# DRV8701ESheet.net
KiCad netlist of a schematic drawn in Altium Designer
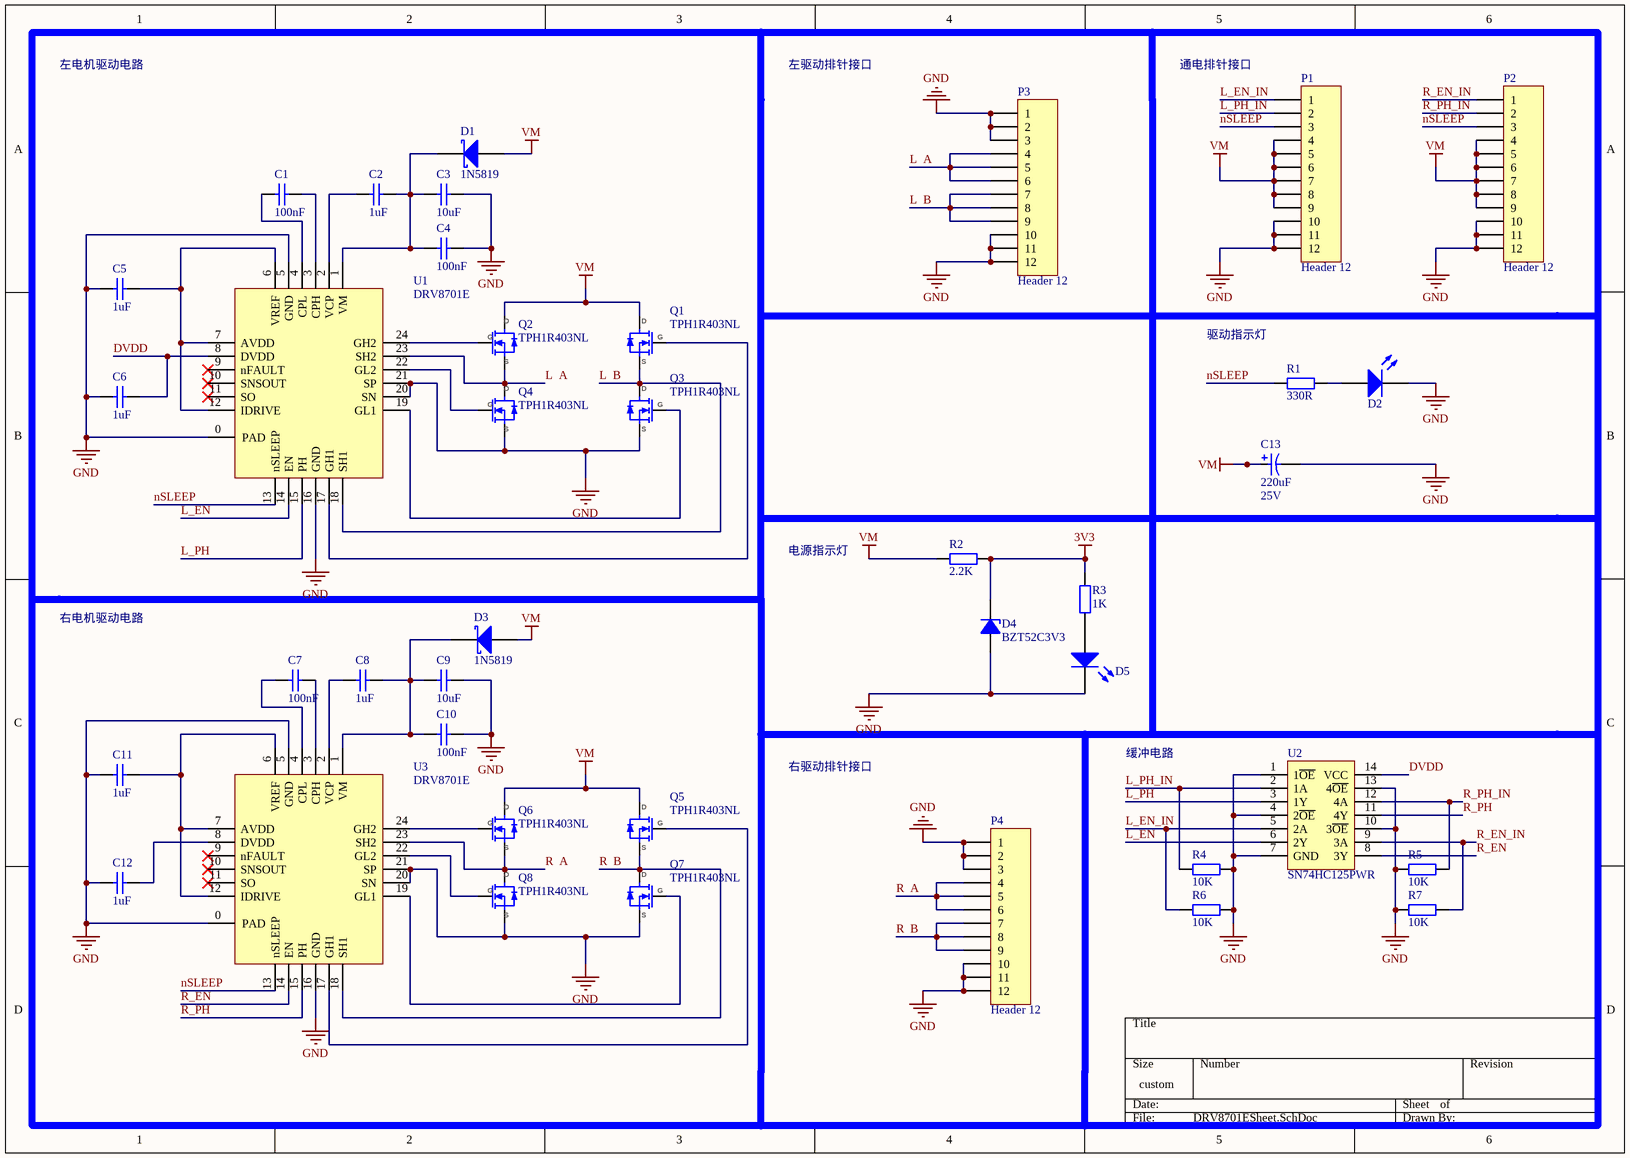
[diagram p0: DRV8701ESheet.SchDoc]

(export (version "E")
  (design (tool "Eeschema 10.0.6"))
  (components
    (comp (ref "C1")
      (value "100nF")
      (footprint "C0603_L")
      (description "贴片电容")
      (libsource (lib "0.1_电容&电感&电阻&保险丝") (part "C-SMD"))
    )
    (comp (ref "C2")
      (value "1uF")
      (footprint "C0603_L")
      (description "贴片电容")
      (libsource (lib "0.1_电容&电感&电阻&保险丝") (part "C-SMD"))
    )
    (comp (ref "C3")
      (value "10uF")
      (footprint "C0603_L")
      (description "贴片电容")
      (libsource (lib "0.1_电容&电感&电阻&保险丝") (part "C-SMD"))
    )
    (comp (ref "C4")
      (value "100nF")
      (footprint "C0603_L")
      (description "贴片电容")
      (libsource (lib "0.1_电容&电感&电阻&保险丝") (part "C-SMD"))
    )
    (comp (ref "C5")
      (value "1uF")
      (footprint "C0603_L")
      (description "贴片电容")
      (libsource (lib "0.1_电容&电感&电阻&保险丝") (part "C-SMD"))
    )
    (comp (ref "C6")
      (value "1uF")
      (footprint "C0603_L")
      (description "贴片电容")
      (libsource (lib "0.1_电容&电感&电阻&保险丝") (part "C-SMD"))
    )
    (comp (ref "C7")
      (value "100nF")
      (footprint "C0603_L")
      (description "贴片电容")
      (libsource (lib "0.1_电容&电感&电阻&保险丝") (part "C-SMD"))
    )
    (comp (ref "C8")
      (value "1uF")
      (footprint "C0603_L")
      (description "贴片电容")
      (libsource (lib "0.1_电容&电感&电阻&保险丝") (part "C-SMD"))
    )
    (comp (ref "C9")
      (value "10uF")
      (footprint "C0603_L")
      (description "贴片电容")
      (libsource (lib "0.1_电容&电感&电阻&保险丝") (part "C-SMD"))
    )
    (comp (ref "C10")
      (value "100nF")
      (footprint "C0603_L")
      (description "贴片电容")
      (libsource (lib "0.1_电容&电感&电阻&保险丝") (part "C-SMD"))
    )
    (comp (ref "C11")
      (value "1uF")
      (footprint "C0603_L")
      (description "贴片电容")
      (libsource (lib "0.1_电容&电感&电阻&保险丝") (part "C-SMD"))
    )
    (comp (ref "C12")
      (value "1uF")
      (footprint "C0603_L")
      (description "贴片电容")
      (libsource (lib "0.1_电容&电感&电阻&保险丝") (part "C-SMD"))
    )
    (comp (ref "C13")
      (value "220uF")
      (footprint "CAPPR3.5-8X11.5")
      (description "Polarized Capacitor (Radial)")
      (fields
        (field (name "VOLTAGE") "25V")
        (field (name "Comment") "220uF 25V")
        (field (name "PUBLISHER") "Altium Limited")
      )
      (libsource (lib "DRV8701E 双驱V1.1 集成封装库") (part "Cap-Elect"))
    )
    (comp (ref "D1")
      (value "1N5819")
      (footprint "SOD-323")
      (description "肖特基二极管")
      (libsource (lib "0.2_二极管&整流桥") (part "1N5819"))
    )
    (comp (ref "D2")
      (value "LED")
      (footprint "LED-0603_R")
      (description "贴片发光二极管")
      (libsource (lib "0.3_LED发光二极管") (part "LED_SMD"))
    )
    (comp (ref "D3")
      (value "1N5819")
      (footprint "SOD-323")
      (description "肖特基二极管")
      (libsource (lib "0.2_二极管&整流桥") (part "1N5819"))
    )
    (comp (ref "D4")
      (value "BZT52C3V3")
      (footprint "SOD-123-L")
      (description "3.3V稳压二极管")
      (fields (field (name "PUBLISHER") "Altium Limited"))
      (libsource (lib "智能车驱动板DRV8701E") (part "Diode Zen"))
    )
    (comp (ref "D5")
      (value "LED")
      (footprint "LED-0603_R")
      (description "贴片发光二极管")
      (libsource (lib "智能车驱动板DRV8701E") (part "LED_SMD"))
    )
    (comp (ref "P1")
      (value "Header 12")
      (footprint "HDR1X12")
      (description "Header, 12-Pin")
      (fields (field (name "PUBLISHER") "Altium Limited"))
      (libsource (lib "Miscellaneous Connectors") (part "Header 12"))
    )
    (comp (ref "P2")
      (value "Header 12")
      (footprint "HDR1X12")
      (description "Header, 12-Pin")
      (fields (field (name "PUBLISHER") "Altium Limited"))
      (libsource (lib "Miscellaneous Connectors") (part "Header 12"))
    )
    (comp (ref "P3")
      (value "Header 12")
      (footprint "HDR1X12")
      (description "Header, 12-Pin")
      (fields (field (name "PUBLISHER") "Altium Limited"))
      (libsource (lib "Miscellaneous Connectors") (part "Header 12"))
    )
    (comp (ref "P4")
      (value "Header 12")
      (footprint "HDR1X12")
      (description "Header, 12-Pin")
      (fields (field (name "PUBLISHER") "Altium Limited"))
      (libsource (lib "Miscellaneous Connectors") (part "Header 12"))
    )
    (comp (ref "Q1")
      (value "TPH1R403NL")
      (footprint "DFN5x6")
      (description "N沟道MOS")
      (libsource (lib "0.4_场效应管&可控硅") (part "TPH1R403NL"))
    )
    (comp (ref "Q2")
      (value "TPH1R403NL")
      (footprint "DFN5x6")
      (description "N沟道MOS")
      (libsource (lib "0.4_场效应管&可控硅") (part "TPH1R403NL"))
    )
    (comp (ref "Q3")
      (value "TPH1R403NL")
      (footprint "DFN5x6")
      (description "N沟道MOS")
      (libsource (lib "0.4_场效应管&可控硅") (part "TPH1R403NL"))
    )
    (comp (ref "Q4")
      (value "TPH1R403NL")
      (footprint "DFN5x6")
      (description "N沟道MOS")
      (libsource (lib "0.4_场效应管&可控硅") (part "TPH1R403NL"))
    )
    (comp (ref "Q5")
      (value "TPH1R403NL")
      (footprint "DFN5x6")
      (description "N沟道MOS")
      (libsource (lib "0.4_场效应管&可控硅") (part "TPH1R403NL"))
    )
    (comp (ref "Q6")
      (value "TPH1R403NL")
      (footprint "DFN5x6")
      (description "N沟道MOS")
      (libsource (lib "0.4_场效应管&可控硅") (part "TPH1R403NL"))
    )
    (comp (ref "Q7")
      (value "TPH1R403NL")
      (footprint "DFN5x6")
      (description "N沟道MOS")
      (libsource (lib "0.4_场效应管&可控硅") (part "TPH1R403NL"))
    )
    (comp (ref "Q8")
      (value "TPH1R403NL")
      (footprint "DFN5x6")
      (description "N沟道MOS")
      (libsource (lib "0.4_场效应管&可控硅") (part "TPH1R403NL"))
    )
    (comp (ref "R1")
      (value "330R")
      (footprint "R0603_L")
      (description "贴片电阻")
      (libsource (lib "0.1_电容&电感&电阻&保险丝") (part "R-SMD"))
    )
    (comp (ref "R2")
      (value "2.2K")
      (footprint "R0603_L")
      (description "贴片电阻")
      (libsource (lib "0.1_电容&电感&电阻&保险丝") (part "R-SMD"))
    )
    (comp (ref "R3")
      (value "1K")
      (footprint "R0603_L")
      (description "贴片电阻")
      (libsource (lib "智能车驱动板DRV8701E") (part "R-SMD"))
    )
    (comp (ref "R4")
      (value "10K")
      (footprint "R0603_L")
      (description "贴片电阻")
      (libsource (lib "0.1_电容&电感&电阻&保险丝") (part "R-SMD"))
    )
    (comp (ref "R5")
      (value "10K")
      (footprint "R0603_L")
      (description "贴片电阻")
      (libsource (lib "0.1_电容&电感&电阻&保险丝") (part "R-SMD"))
    )
    (comp (ref "R6")
      (value "10K")
      (footprint "R0603_L")
      (description "贴片电阻")
      (libsource (lib "0.1_电容&电感&电阻&保险丝") (part "R-SMD"))
    )
    (comp (ref "R7")
      (value "10K")
      (footprint "R0603_L")
      (description "贴片电阻")
      (libsource (lib "0.1_电容&电感&电阻&保险丝") (part "R-SMD"))
    )
    (comp (ref "U1")
      (value "DRV8701E")
      (footprint "QFN24-4x4")
      (description "DRV8701E Ti全桥驱动芯片")
      (libsource (lib "智能车驱动板DRV8701E") (part "DRV8701E"))
    )
    (comp (ref "U2")
      (value "SN74HC125PWR")
      (footprint "TSSOP14")
      (description "三态输出的四路缓冲器")
      (libsource (lib "智能车驱动板DRV8701E") (part "SN74HC125PWR"))
    )
    (comp (ref "U3")
      (value "DRV8701E")
      (footprint "QFN24-4x4")
      (description "DRV8701E Ti全桥驱动芯片")
      (libsource (lib "智能车驱动板DRV8701E") (part "DRV8701E"))
    )
  )
  (nets
    (net (code "1") (name "/DVDD") (class "Default")
      (node (ref "C6") (pin "2") (pinfunction "2_2") (pintype "passive"))
      (node (ref "U1") (pin "8") (pinfunction "DVDD_8") (pintype "passive"))
      (node (ref "U2") (pin "14") (pinfunction "VCC_14") (pintype "passive"))
    )
    (net (code "2") (name "/L  A") (class "Default")
      (node (ref "P3") (pin "4") (pinfunction "4_4") (pintype "passive"))
      (node (ref "P3") (pin "5") (pinfunction "5_5") (pintype "passive"))
      (node (ref "P3") (pin "6") (pinfunction "6_6") (pintype "passive"))
      (node (ref "Q2") (pin "3") (pinfunction "S_3") (pintype "passive"))
      (node (ref "Q4") (pin "1") (pinfunction "D_1") (pintype "passive"))
      (node (ref "U1") (pin "23") (pinfunction "SH2_23") (pintype "passive"))
    )
    (net (code "3") (name "/L  B") (class "Default")
      (node (ref "P3") (pin "7") (pinfunction "7_7") (pintype "passive"))
      (node (ref "P3") (pin "8") (pinfunction "8_8") (pintype "passive"))
      (node (ref "P3") (pin "9") (pinfunction "9_9") (pintype "passive"))
      (node (ref "Q1") (pin "3") (pinfunction "S_3") (pintype "passive"))
      (node (ref "Q3") (pin "1") (pinfunction "D_1") (pintype "passive"))
      (node (ref "U1") (pin "18") (pinfunction "SH1_18") (pintype "passive"))
    )
    (net (code "4") (name "/L_EN") (class "Default")
      (node (ref "U1") (pin "14") (pinfunction "EN_14") (pintype "passive"))
      (node (ref "U2") (pin "6") (pinfunction "2Y_6") (pintype "passive"))
    )
    (net (code "5") (name "/L_EN_IN") (class "Default")
      (node (ref "P1") (pin "1") (pinfunction "1_1") (pintype "passive"))
      (node (ref "R6") (pin "1") (pinfunction "1_1") (pintype "passive"))
      (node (ref "U2") (pin "5") (pinfunction "2A_5") (pintype "passive"))
    )
    (net (code "6") (name "/L_PH") (class "Default")
      (node (ref "U1") (pin "15") (pinfunction "PH_15") (pintype "passive"))
      (node (ref "U2") (pin "3") (pinfunction "1Y_3") (pintype "passive"))
    )
    (net (code "7") (name "/L_PH_IN") (class "Default")
      (node (ref "P1") (pin "2") (pinfunction "2_2") (pintype "passive"))
      (node (ref "R4") (pin "1") (pinfunction "1_1") (pintype "passive"))
      (node (ref "U2") (pin "2") (pinfunction "1A_2") (pintype "passive"))
    )
    (net (code "8") (name "/R  A") (class "Default")
      (node (ref "P4") (pin "4") (pinfunction "4_4") (pintype "passive"))
      (node (ref "P4") (pin "5") (pinfunction "5_5") (pintype "passive"))
      (node (ref "P4") (pin "6") (pinfunction "6_6") (pintype "passive"))
      (node (ref "Q6") (pin "3") (pinfunction "S_3") (pintype "passive"))
      (node (ref "Q8") (pin "1") (pinfunction "D_1") (pintype "passive"))
      (node (ref "U3") (pin "23") (pinfunction "SH2_23") (pintype "passive"))
    )
    (net (code "9") (name "/R  B") (class "Default")
      (node (ref "P4") (pin "7") (pinfunction "7_7") (pintype "passive"))
      (node (ref "P4") (pin "8") (pinfunction "8_8") (pintype "passive"))
      (node (ref "P4") (pin "9") (pinfunction "9_9") (pintype "passive"))
      (node (ref "Q5") (pin "3") (pinfunction "S_3") (pintype "passive"))
      (node (ref "Q7") (pin "1") (pinfunction "D_1") (pintype "passive"))
      (node (ref "U3") (pin "18") (pinfunction "SH1_18") (pintype "passive"))
    )
    (net (code "10") (name "/R_EN") (class "Default")
      (node (ref "U2") (pin "8") (pinfunction "3Y_8") (pintype "passive"))
      (node (ref "U3") (pin "14") (pinfunction "EN_14") (pintype "passive"))
    )
    (net (code "11") (name "/R_EN_IN") (class "Default")
      (node (ref "P2") (pin "1") (pinfunction "1_1") (pintype "passive"))
      (node (ref "R7") (pin "2") (pinfunction "2_2") (pintype "passive"))
      (node (ref "U2") (pin "9") (pinfunction "3A_9") (pintype "passive"))
    )
    (net (code "12") (name "/R_PH") (class "Default")
      (node (ref "U2") (pin "11") (pinfunction "4Y_11") (pintype "passive"))
      (node (ref "U3") (pin "15") (pinfunction "PH_15") (pintype "passive"))
    )
    (net (code "13") (name "/R_PH_IN") (class "Default")
      (node (ref "P2") (pin "2") (pinfunction "2_2") (pintype "passive"))
      (node (ref "R5") (pin "2") (pinfunction "2_2") (pintype "passive"))
      (node (ref "U2") (pin "12") (pinfunction "4A_12") (pintype "passive"))
    )
    (net (code "14") (name "/nSLEEP") (class "Default")
      (node (ref "P1") (pin "3") (pinfunction "3_3") (pintype "passive"))
      (node (ref "P2") (pin "3") (pinfunction "3_3") (pintype "passive"))
      (node (ref "R1") (pin "1") (pinfunction "1_1") (pintype "passive"))
      (node (ref "U1") (pin "13") (pinfunction "nSLEEP_13") (pintype "passive"))
      (node (ref "U3") (pin "13") (pinfunction "nSLEEP_13") (pintype "passive"))
    )
    (net (code "15") (name "3V3") (class "Default")
      (node (ref "D4") (pin "K") (pinfunction "K_K") (pintype "passive"))
      (node (ref "R2") (pin "2") (pinfunction "2_2") (pintype "passive"))
      (node (ref "R3") (pin "2") (pinfunction "2_2") (pintype "passive"))
    )
    (net (code "16") (name "GND") (class "Default")
      (node (ref "C10") (pin "2") (pinfunction "2_2") (pintype "passive"))
      (node (ref "C11") (pin "1") (pinfunction "1_1") (pintype "passive"))
      (node (ref "C12") (pin "1") (pinfunction "1_1") (pintype "passive"))
      (node (ref "C13") (pin "2") (pinfunction "2_2") (pintype "passive"))
      (node (ref "C3") (pin "2") (pinfunction "2_2") (pintype "passive"))
      (node (ref "C4") (pin "2") (pinfunction "2_2") (pintype "passive"))
      (node (ref "C5") (pin "1") (pinfunction "1_1") (pintype "passive"))
      (node (ref "C6") (pin "1") (pinfunction "1_1") (pintype "passive"))
      (node (ref "C9") (pin "2") (pinfunction "2_2") (pintype "passive"))
      (node (ref "D2") (pin "2") (pinfunction "K_2") (pintype "passive"))
      (node (ref "D4") (pin "A") (pinfunction "A_A") (pintype "passive"))
      (node (ref "D5") (pin "2") (pinfunction "K_2") (pintype "passive"))
      (node (ref "P1") (pin "10") (pinfunction "10_10") (pintype "passive"))
      (node (ref "P1") (pin "11") (pinfunction "11_11") (pintype "passive"))
      (node (ref "P1") (pin "12") (pinfunction "12_12") (pintype "passive"))
      (node (ref "P2") (pin "10") (pinfunction "10_10") (pintype "passive"))
      (node (ref "P2") (pin "11") (pinfunction "11_11") (pintype "passive"))
      (node (ref "P2") (pin "12") (pinfunction "12_12") (pintype "passive"))
      (node (ref "P3") (pin "1") (pinfunction "1_1") (pintype "passive"))
      (node (ref "P3") (pin "10") (pinfunction "10_10") (pintype "passive"))
      (node (ref "P3") (pin "11") (pinfunction "11_11") (pintype "passive"))
      (node (ref "P3") (pin "12") (pinfunction "12_12") (pintype "passive"))
      (node (ref "P3") (pin "2") (pinfunction "2_2") (pintype "passive"))
      (node (ref "P3") (pin "3") (pinfunction "3_3") (pintype "passive"))
      (node (ref "P4") (pin "1") (pinfunction "1_1") (pintype "passive"))
      (node (ref "P4") (pin "10") (pinfunction "10_10") (pintype "passive"))
      (node (ref "P4") (pin "11") (pinfunction "11_11") (pintype "passive"))
      (node (ref "P4") (pin "12") (pinfunction "12_12") (pintype "passive"))
      (node (ref "P4") (pin "2") (pinfunction "2_2") (pintype "passive"))
      (node (ref "P4") (pin "3") (pinfunction "3_3") (pintype "passive"))
      (node (ref "Q3") (pin "3") (pinfunction "S_3") (pintype "passive"))
      (node (ref "Q4") (pin "3") (pinfunction "S_3") (pintype "passive"))
      (node (ref "Q7") (pin "3") (pinfunction "S_3") (pintype "passive"))
      (node (ref "Q8") (pin "3") (pinfunction "S_3") (pintype "passive"))
      (node (ref "R4") (pin "2") (pinfunction "2_2") (pintype "passive"))
      (node (ref "R5") (pin "1") (pinfunction "1_1") (pintype "passive"))
      (node (ref "R6") (pin "2") (pinfunction "2_2") (pintype "passive"))
      (node (ref "R7") (pin "1") (pinfunction "1_1") (pintype "passive"))
      (node (ref "U1") (pin "0") (pinfunction "PAD_0") (pintype "passive"))
      (node (ref "U1") (pin "16") (pinfunction "GND_16") (pintype "passive"))
      (node (ref "U1") (pin "20") (pinfunction "SN_20") (pintype "passive"))
      (node (ref "U1") (pin "21") (pinfunction "SP_21") (pintype "passive"))
      (node (ref "U1") (pin "5") (pinfunction "GND_5") (pintype "passive"))
      (node (ref "U2") (pin "1") (pinfunction "1~{OE}_1") (pintype "passive"))
      (node (ref "U2") (pin "10") (pinfunction "3~{OE}_10") (pintype "passive"))
      (node (ref "U2") (pin "13") (pinfunction "4~{OE}_13") (pintype "passive"))
      (node (ref "U2") (pin "4") (pinfunction "2~{OE}_4") (pintype "passive"))
      (node (ref "U2") (pin "7") (pinfunction "GND_7") (pintype "passive"))
      (node (ref "U3") (pin "0") (pinfunction "PAD_0") (pintype "passive"))
      (node (ref "U3") (pin "16") (pinfunction "GND_16") (pintype "passive"))
      (node (ref "U3") (pin "20") (pinfunction "SN_20") (pintype "passive"))
      (node (ref "U3") (pin "21") (pinfunction "SP_21") (pintype "passive"))
      (node (ref "U3") (pin "5") (pinfunction "GND_5") (pintype "passive"))
    )
    (net (code "17") (name "Net-(D1-K)") (class "Default")
      (node (ref "C2") (pin "2") (pinfunction "2_2") (pintype "passive"))
      (node (ref "C3") (pin "1") (pinfunction "1_1") (pintype "passive"))
      (node (ref "C4") (pin "1") (pinfunction "1_1") (pintype "passive"))
      (node (ref "D1") (pin "2") (pinfunction "K_2") (pintype "passive"))
      (node (ref "U1") (pin "1") (pinfunction "VM_1") (pintype "passive"))
    )
    (net (code "18") (name "Net-(D2-A)") (class "Default")
      (node (ref "D2") (pin "1") (pinfunction "A_1") (pintype "passive"))
      (node (ref "R1") (pin "2") (pinfunction "2_2") (pintype "passive"))
    )
    (net (code "19") (name "Net-(D3-K)") (class "Default")
      (node (ref "C10") (pin "1") (pinfunction "1_1") (pintype "passive"))
      (node (ref "C8") (pin "2") (pinfunction "2_2") (pintype "passive"))
      (node (ref "C9") (pin "1") (pinfunction "1_1") (pintype "passive"))
      (node (ref "D3") (pin "2") (pinfunction "K_2") (pintype "passive"))
      (node (ref "U3") (pin "1") (pinfunction "VM_1") (pintype "passive"))
    )
    (net (code "20") (name "Net-(D5-A)") (class "Default")
      (node (ref "D5") (pin "1") (pinfunction "A_1") (pintype "passive"))
      (node (ref "R3") (pin "1") (pinfunction "1_1") (pintype "passive"))
    )
    (net (code "21") (name "Net-(Q1-G)") (class "Default")
      (node (ref "Q1") (pin "2") (pinfunction "G_2") (pintype "passive"))
      (node (ref "U1") (pin "17") (pinfunction "GH1_17") (pintype "passive"))
    )
    (net (code "22") (name "Net-(Q2-G)") (class "Default")
      (node (ref "Q2") (pin "2") (pinfunction "G_2") (pintype "passive"))
      (node (ref "U1") (pin "24") (pinfunction "GH2_24") (pintype "passive"))
    )
    (net (code "23") (name "Net-(Q3-G)") (class "Default")
      (node (ref "Q3") (pin "2") (pinfunction "G_2") (pintype "passive"))
      (node (ref "U1") (pin "19") (pinfunction "GL1_19") (pintype "passive"))
    )
    (net (code "24") (name "Net-(Q4-G)") (class "Default")
      (node (ref "Q4") (pin "2") (pinfunction "G_2") (pintype "passive"))
      (node (ref "U1") (pin "22") (pinfunction "GL2_22") (pintype "passive"))
    )
    (net (code "25") (name "Net-(Q5-G)") (class "Default")
      (node (ref "Q5") (pin "2") (pinfunction "G_2") (pintype "passive"))
      (node (ref "U3") (pin "17") (pinfunction "GH1_17") (pintype "passive"))
    )
    (net (code "26") (name "Net-(Q6-G)") (class "Default")
      (node (ref "Q6") (pin "2") (pinfunction "G_2") (pintype "passive"))
      (node (ref "U3") (pin "24") (pinfunction "GH2_24") (pintype "passive"))
    )
    (net (code "27") (name "Net-(Q7-G)") (class "Default")
      (node (ref "Q7") (pin "2") (pinfunction "G_2") (pintype "passive"))
      (node (ref "U3") (pin "19") (pinfunction "GL1_19") (pintype "passive"))
    )
    (net (code "28") (name "Net-(Q8-G)") (class "Default")
      (node (ref "Q8") (pin "2") (pinfunction "G_2") (pintype "passive"))
      (node (ref "U3") (pin "22") (pinfunction "GL2_22") (pintype "passive"))
    )
    (net (code "29") (name "Net-(U1-AVDD)") (class "Default")
      (node (ref "C5") (pin "2") (pinfunction "2_2") (pintype "passive"))
      (node (ref "U1") (pin "12") (pinfunction "IDRIVE_12") (pintype "passive"))
      (node (ref "U1") (pin "6") (pinfunction "VREF_6") (pintype "passive"))
      (node (ref "U1") (pin "7") (pinfunction "AVDD_7") (pintype "passive"))
    )
    (net (code "30") (name "Net-(U1-CPH)") (class "Default")
      (node (ref "C1") (pin "2") (pinfunction "2_2") (pintype "passive"))
      (node (ref "U1") (pin "3") (pinfunction "CPH_3") (pintype "passive"))
    )
    (net (code "31") (name "Net-(U1-CPL)") (class "Default")
      (node (ref "C1") (pin "1") (pinfunction "1_1") (pintype "passive"))
      (node (ref "U1") (pin "4") (pinfunction "CPL_4") (pintype "passive"))
    )
    (net (code "32") (name "Net-(U1-VCP)") (class "Default")
      (node (ref "C2") (pin "1") (pinfunction "1_1") (pintype "passive"))
      (node (ref "U1") (pin "2") (pinfunction "VCP_2") (pintype "passive"))
    )
    (net (code "33") (name "Net-(U3-AVDD)") (class "Default")
      (node (ref "C11") (pin "2") (pinfunction "2_2") (pintype "passive"))
      (node (ref "U3") (pin "12") (pinfunction "IDRIVE_12") (pintype "passive"))
      (node (ref "U3") (pin "6") (pinfunction "VREF_6") (pintype "passive"))
      (node (ref "U3") (pin "7") (pinfunction "AVDD_7") (pintype "passive"))
    )
    (net (code "34") (name "Net-(U3-CPH)") (class "Default")
      (node (ref "C7") (pin "2") (pinfunction "2_2") (pintype "passive"))
      (node (ref "U3") (pin "3") (pinfunction "CPH_3") (pintype "passive"))
    )
    (net (code "35") (name "Net-(U3-CPL)") (class "Default")
      (node (ref "C7") (pin "1") (pinfunction "1_1") (pintype "passive"))
      (node (ref "U3") (pin "4") (pinfunction "CPL_4") (pintype "passive"))
    )
    (net (code "36") (name "Net-(U3-DVDD)") (class "Default")
      (node (ref "C12") (pin "2") (pinfunction "2_2") (pintype "passive"))
      (node (ref "U3") (pin "8") (pinfunction "DVDD_8") (pintype "passive"))
    )
    (net (code "37") (name "Net-(U3-VCP)") (class "Default")
      (node (ref "C8") (pin "1") (pinfunction "1_1") (pintype "passive"))
      (node (ref "U3") (pin "2") (pinfunction "VCP_2") (pintype "passive"))
    )
    (net (code "38") (name "VM") (class "Default")
      (node (ref "C13") (pin "1") (pinfunction "1_1") (pintype "passive"))
      (node (ref "D1") (pin "1") (pinfunction "A_1") (pintype "passive"))
      (node (ref "D3") (pin "1") (pinfunction "A_1") (pintype "passive"))
      (node (ref "P1") (pin "4") (pinfunction "4_4") (pintype "passive"))
      (node (ref "P1") (pin "5") (pinfunction "5_5") (pintype "passive"))
      (node (ref "P1") (pin "6") (pinfunction "6_6") (pintype "passive"))
      (node (ref "P1") (pin "7") (pinfunction "7_7") (pintype "passive"))
      (node (ref "P1") (pin "8") (pinfunction "8_8") (pintype "passive"))
      (node (ref "P1") (pin "9") (pinfunction "9_9") (pintype "passive"))
      (node (ref "P2") (pin "4") (pinfunction "4_4") (pintype "passive"))
      (node (ref "P2") (pin "5") (pinfunction "5_5") (pintype "passive"))
      (node (ref "P2") (pin "6") (pinfunction "6_6") (pintype "passive"))
      (node (ref "P2") (pin "7") (pinfunction "7_7") (pintype "passive"))
      (node (ref "P2") (pin "8") (pinfunction "8_8") (pintype "passive"))
      (node (ref "P2") (pin "9") (pinfunction "9_9") (pintype "passive"))
      (node (ref "Q1") (pin "1") (pinfunction "D_1") (pintype "passive"))
      (node (ref "Q2") (pin "1") (pinfunction "D_1") (pintype "passive"))
      (node (ref "Q5") (pin "1") (pinfunction "D_1") (pintype "passive"))
      (node (ref "Q6") (pin "1") (pinfunction "D_1") (pintype "passive"))
      (node (ref "R2") (pin "1") (pinfunction "1_1") (pintype "passive"))
    )
    (net (code "39") (name "unconnected-(U1-SNSOUT-Pad10)") (class "Default")
      (node (ref "U1") (pin "10") (pinfunction "SNSOUT_10") (pintype "passive+no_connect"))
    )
    (net (code "40") (name "unconnected-(U1-SO-Pad11)") (class "Default")
      (node (ref "U1") (pin "11") (pinfunction "SO_11") (pintype "passive+no_connect"))
    )
    (net (code "41") (name "unconnected-(U1-nFAULT-Pad9)") (class "Default")
      (node (ref "U1") (pin "9") (pinfunction "nFAULT_9") (pintype "passive+no_connect"))
    )
    (net (code "42") (name "unconnected-(U3-SNSOUT-Pad10)") (class "Default")
      (node (ref "U3") (pin "10") (pinfunction "SNSOUT_10") (pintype "passive+no_connect"))
    )
    (net (code "43") (name "unconnected-(U3-SO-Pad11)") (class "Default")
      (node (ref "U3") (pin "11") (pinfunction "SO_11") (pintype "passive+no_connect"))
    )
    (net (code "44") (name "unconnected-(U3-nFAULT-Pad9)") (class "Default")
      (node (ref "U3") (pin "9") (pinfunction "nFAULT_9") (pintype "passive+no_connect"))
    )
  )
)
